# POV3_singleside.net
KiCad netlist of a schematic drawn in EAGLE
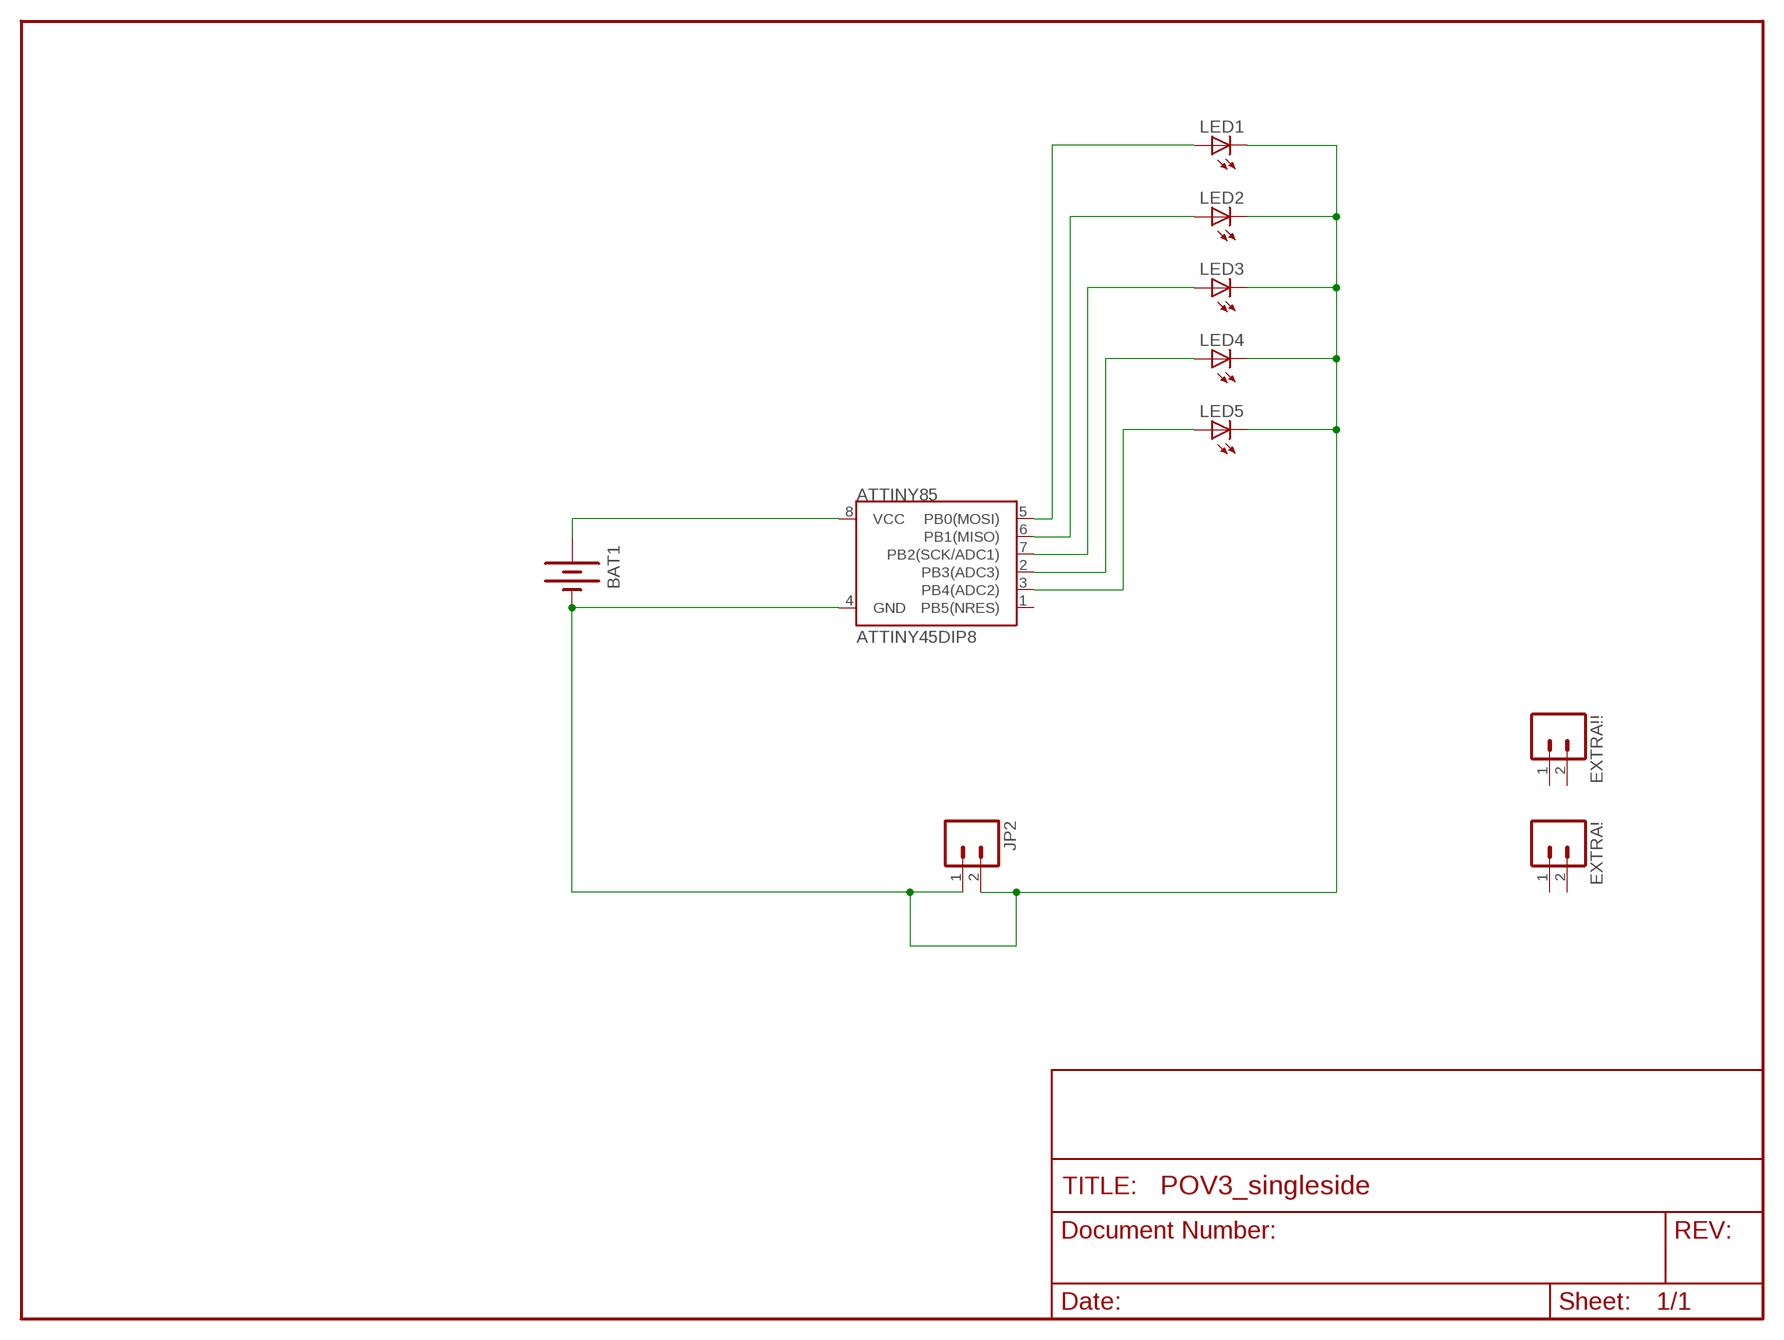
[diagram p0: schematic, sheet 1]

(export (version "E")
  (design (tool "Eeschema 10.0.6"))
  (components
    (comp (ref "ATTINY85")
      (value "ATTINY45DIP8")
      (footprint "eagle-import:DIP08")
      (libsource (lib "eagle-import") (part "ATTINY45DIP8"))
    )
    (comp (ref "BAT1")
      (value "BATTERY20PTH")
      (footprint "eagle-import:BATTCOM_20MM_PTH")
      (libsource (lib "eagle-import") (part "BATTERY20PTH"))
    )
    (comp (ref "EXTRA!")
      (value "M02PTH")
      (footprint "eagle-import:1X02")
      (libsource (lib "eagle-import") (part "M02PTH"))
    )
    (comp (ref "EXTRA!!")
      (value "M02PTH")
      (footprint "eagle-import:1X02")
      (libsource (lib "eagle-import") (part "M02PTH"))
    )
    (comp (ref "JP2")
      (value "M02PTH")
      (footprint "eagle-import:1X02")
      (libsource (lib "eagle-import") (part "M02PTH"))
    )
    (comp (ref "LED1")
      (value "LED5MM")
      (footprint "eagle-import:LED5MM")
      (libsource (lib "eagle-import") (part "LED5MM"))
    )
    (comp (ref "LED2")
      (value "LED5MM")
      (footprint "eagle-import:LED5MM")
      (libsource (lib "eagle-import") (part "LED5MM"))
    )
    (comp (ref "LED3")
      (value "LED5MM")
      (footprint "eagle-import:LED5MM")
      (libsource (lib "eagle-import") (part "LED5MM"))
    )
    (comp (ref "LED4")
      (value "LED5MM")
      (footprint "eagle-import:LED5MM")
      (libsource (lib "eagle-import") (part "LED5MM"))
    )
    (comp (ref "LED5")
      (value "LED5MM")
      (footprint "eagle-import:LED5MM")
      (libsource (lib "eagle-import") (part "LED5MM"))
    )
  )
  (nets
    (net (code "1") (name "Net-(ATTINY85-GND)") (class "Default")
      (node (ref "ATTINY85") (pin "4") (pinfunction "GND_4") (pintype "bidirectional"))
      (node (ref "BAT1") (pin "2") (pinfunction "-_2") (pintype "power_in"))
      (node (ref "JP2") (pin "1") (pinfunction "1_1") (pintype "passive"))
      (node (ref "JP2") (pin "2") (pinfunction "2_2") (pintype "passive"))
      (node (ref "LED1") (pin "K") (pinfunction "C_K") (pintype "passive"))
      (node (ref "LED2") (pin "K") (pinfunction "C_K") (pintype "passive"))
      (node (ref "LED3") (pin "K") (pinfunction "C_K") (pintype "passive"))
      (node (ref "LED4") (pin "K") (pinfunction "C_K") (pintype "passive"))
      (node (ref "LED5") (pin "K") (pinfunction "C_K") (pintype "passive"))
    )
    (net (code "2") (name "Net-(ATTINY85-PB0(MOSI))") (class "Default")
      (node (ref "ATTINY85") (pin "5") (pinfunction "PB0(MOSI)_5") (pintype "bidirectional"))
      (node (ref "LED1") (pin "A") (pinfunction "A_A") (pintype "passive"))
    )
    (net (code "3") (name "Net-(ATTINY85-PB1(MISO))") (class "Default")
      (node (ref "ATTINY85") (pin "6") (pinfunction "PB1(MISO)_6") (pintype "bidirectional"))
      (node (ref "LED2") (pin "A") (pinfunction "A_A") (pintype "passive"))
    )
    (net (code "4") (name "Net-(ATTINY85-PB2(SCK{slash}ADC1))") (class "Default")
      (node (ref "ATTINY85") (pin "7") (pinfunction "PB2(SCK/ADC1)_7") (pintype "bidirectional"))
      (node (ref "LED3") (pin "A") (pinfunction "A_A") (pintype "passive"))
    )
    (net (code "5") (name "Net-(ATTINY85-PB3(ADC3))") (class "Default")
      (node (ref "ATTINY85") (pin "2") (pinfunction "PB3(ADC3)_2") (pintype "bidirectional"))
      (node (ref "LED4") (pin "A") (pinfunction "A_A") (pintype "passive"))
    )
    (net (code "6") (name "Net-(ATTINY85-PB4(ADC2))") (class "Default")
      (node (ref "ATTINY85") (pin "3") (pinfunction "PB4(ADC2)_3") (pintype "bidirectional"))
      (node (ref "LED5") (pin "A") (pinfunction "A_A") (pintype "passive"))
    )
    (net (code "7") (name "Net-(ATTINY85-VCC)") (class "Default")
      (node (ref "ATTINY85") (pin "8") (pinfunction "VCC_8") (pintype "bidirectional"))
      (node (ref "BAT1") (pin "1") (pinfunction "+_1") (pintype "power_in"))
    )
    (net (code "8") (name "unconnected-(ATTINY85-PB5(NRES)-Pad1)") (class "Default")
      (node (ref "ATTINY85") (pin "1") (pinfunction "PB5(NRES)_1") (pintype "bidirectional"))
    )
    (net (code "9") (name "unconnected-(EXTRA!!-Pad1)") (class "Default")
      (node (ref "EXTRA!!") (pin "1") (pinfunction "1_1") (pintype "passive"))
    )
    (net (code "10") (name "unconnected-(EXTRA!!-Pad2)") (class "Default")
      (node (ref "EXTRA!!") (pin "2") (pinfunction "2_2") (pintype "passive"))
    )
    (net (code "11") (name "unconnected-(EXTRA!-Pad1)") (class "Default")
      (node (ref "EXTRA!") (pin "1") (pinfunction "1_1") (pintype "passive"))
    )
    (net (code "12") (name "unconnected-(EXTRA!-Pad2)") (class "Default")
      (node (ref "EXTRA!") (pin "2") (pinfunction "2_2") (pintype "passive"))
    )
  )
)
